# CarCharger.net
KiCad netlist of a schematic drawn in Altium Designer
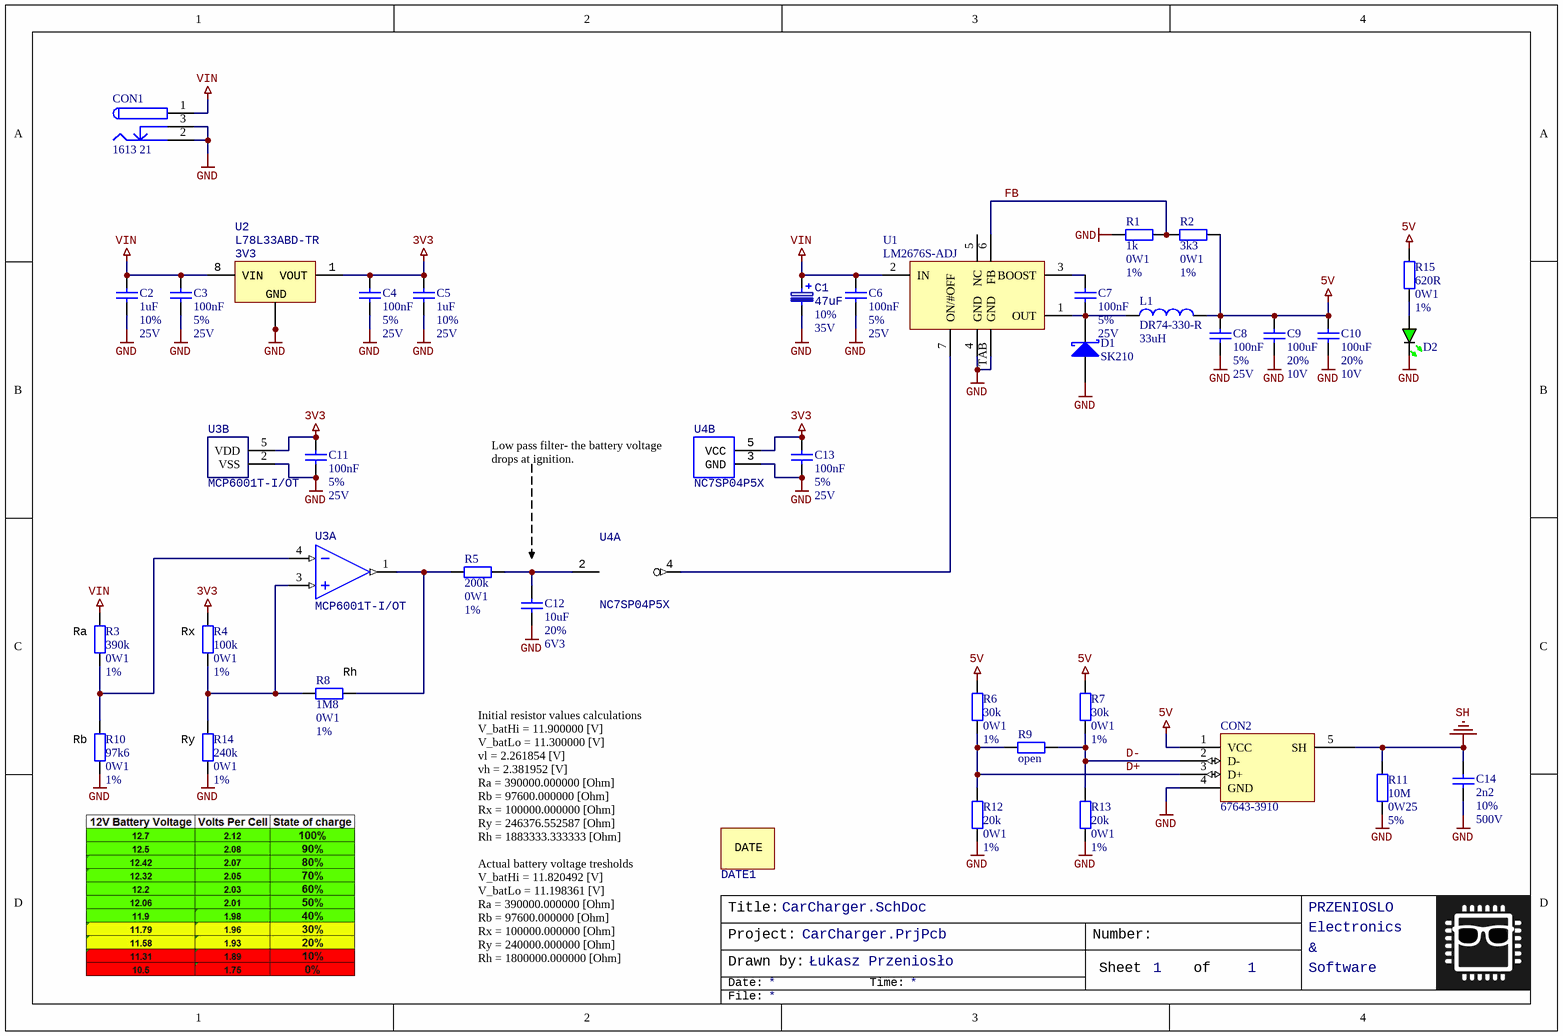
[diagram p0: CarCharger.SchDoc]

(export (version "E")
  (design (tool "Eeschema 10.0.6"))
  (components
    (comp (ref "C1")
      (value "47uF")
      (footprint "SMDD")
      (fields (field (name "TOLERANCE") "10%") (field (name "VOLTAGE") "35V"))
      (libsource (lib "passives") (part "cap_electro"))
    )
    (comp (ref "C2")
      (value "1uF")
      (footprint "CAPC1608N")
      (description "Capacitor")
      (fields (field (name "TOLERANCE") "10%") (field (name "VOLTAGE") "25V"))
      (libsource (lib "passives") (part "Capacitor"))
    )
    (comp (ref "C3")
      (value "100nF")
      (footprint "CAPC1608N")
      (description "Capacitor")
      (fields (field (name "TOLERANCE") "5%") (field (name "VOLTAGE") "25V"))
      (libsource (lib "passives") (part "Capacitor"))
    )
    (comp (ref "C4")
      (value "100nF")
      (footprint "CAPC1608N")
      (description "Capacitor")
      (fields (field (name "TOLERANCE") "5%") (field (name "VOLTAGE") "25V"))
      (libsource (lib "passives") (part "Capacitor"))
    )
    (comp (ref "C5")
      (value "1uF")
      (footprint "CAPC1608N")
      (description "Capacitor")
      (fields (field (name "TOLERANCE") "10%") (field (name "VOLTAGE") "25V"))
      (libsource (lib "passives") (part "Capacitor"))
    )
    (comp (ref "C6")
      (value "100nF")
      (footprint "CAPC1608N")
      (description "Capacitor")
      (fields (field (name "TOLERANCE") "5%") (field (name "VOLTAGE") "25V"))
      (libsource (lib "passives") (part "Capacitor"))
    )
    (comp (ref "C7")
      (value "100nF")
      (footprint "CAPC1608N")
      (description "Capacitor")
      (fields (field (name "TOLERANCE") "5%") (field (name "VOLTAGE") "25V"))
      (libsource (lib "passives") (part "Capacitor"))
    )
    (comp (ref "C8")
      (value "100nF")
      (footprint "CAPC1608N")
      (description "Capacitor")
      (fields (field (name "TOLERANCE") "5%") (field (name "VOLTAGE") "25V"))
      (libsource (lib "passives") (part "Capacitor"))
    )
    (comp (ref "C9")
      (value "100uF")
      (footprint "CAPC3225N")
      (description "Capacitor")
      (fields (field (name "TOLERANCE") "20%") (field (name "VOLTAGE") "10V"))
      (libsource (lib "passives") (part "Capacitor"))
    )
    (comp (ref "C10")
      (value "100uF")
      (footprint "CAPC3225N")
      (description "Capacitor")
      (fields (field (name "TOLERANCE") "20%") (field (name "VOLTAGE") "10V"))
      (libsource (lib "passives") (part "Capacitor"))
    )
    (comp (ref "C11")
      (value "100nF")
      (footprint "CAPC1608N")
      (description "Capacitor")
      (fields (field (name "TOLERANCE") "5%") (field (name "VOLTAGE") "25V"))
      (libsource (lib "passives") (part "Capacitor"))
    )
    (comp (ref "C12")
      (value "10uF")
      (footprint "CAPC1608N")
      (description "Capacitor")
      (fields (field (name "TOLERANCE") "20%") (field (name "VOLTAGE") "6V3"))
      (libsource (lib "passives") (part "Capacitor"))
    )
    (comp (ref "C13")
      (value "100nF")
      (footprint "CAPC1608N")
      (description "Capacitor")
      (fields (field (name "TOLERANCE") "5%") (field (name "VOLTAGE") "25V"))
      (libsource (lib "passives") (part "Capacitor"))
    )
    (comp (ref "C14")
      (value "2n2")
      (footprint "CAPC3216N")
      (description "Capacitor")
      (fields (field (name "TOLERANCE") "10%") (field (name "VOLTAGE") "500V"))
      (libsource (lib "passives") (part "Capacitor"))
    )
    (comp (ref "CON1")
      (value "1613 21")
      (footprint "JACK-2.5")
      (description "Low Voltage Power Supply Connector")
      (libsource (lib "connectors") (part "JACK-2.5"))
    )
    (comp (ref "CON2")
      (value "67643-3910")
      (footprint "USB-A-socket")
      (description "USB-A-Sock")
      (libsource (lib "connectors") (part "USB-A-Sock"))
    )
    (comp (ref "D1")
      (value "SK210")
      (footprint "SMB")
      (description "Schottky Barrier Rectifier,  40V, 3A")
      (libsource (lib "Mechatronic") (part "MBRS340T3"))
    )
    (comp (ref "D2")
      (value "Led Green")
      (footprint "CD2012-0805-GRN")
      (description "Typical GRN LED")
      (libsource (lib "semicon") (part "Led Green"))
    )
    (comp (ref "DATE1") (value "DATE") (footprint "DATE") (libsource (lib "misc") (part "DATE")))
    (comp (ref "L1")
      (value "DR74-330-R")
      (footprint "DR74 Series")
      (fields (field (name "ALTIUM_VALUE") "33uH") (field (name "PUBLISHER") "Altium Limited"))
      (libsource (lib "Mechatronic") (part "DR74-330-R"))
    )
    (comp (ref "R1")
      (value "1k")
      (footprint "RESC1608N")
      (description "Resistor")
      (fields (field (name "POWER") "0W1") (field (name "TOLERANCE") "1%"))
      (libsource (lib "") (part "Resistor_1"))
    )
    (comp (ref "R2")
      (value "3k3")
      (footprint "RESC1608N")
      (description "Resistor")
      (fields (field (name "POWER") "0W1") (field (name "TOLERANCE") "1%"))
      (libsource (lib "") (part "Resistor_1"))
    )
    (comp (ref "R3")
      (value "390k")
      (footprint "RESC1608N")
      (description "Resistor")
      (fields (field (name "POWER") "0W1") (field (name "TOLERANCE") "1%"))
      (libsource (lib "passives") (part "Resistor"))
    )
    (comp (ref "R4")
      (value "100k")
      (footprint "RESC1608N")
      (description "Resistor")
      (fields (field (name "POWER") "0W1") (field (name "TOLERANCE") "1%"))
      (libsource (lib "passives") (part "Resistor"))
    )
    (comp (ref "R5")
      (value "200k")
      (footprint "RESC1608N")
      (description "Resistor")
      (fields (field (name "POWER") "0W1") (field (name "TOLERANCE") "1%"))
      (libsource (lib "") (part "Resistor_1"))
    )
    (comp (ref "R6")
      (value "30k")
      (footprint "RESC1608N")
      (description "Resistor")
      (fields (field (name "POWER") "0W1") (field (name "TOLERANCE") "1%"))
      (libsource (lib "passives") (part "Resistor"))
    )
    (comp (ref "R7")
      (value "30k")
      (footprint "RESC1608N")
      (description "Resistor")
      (fields (field (name "POWER") "0W1") (field (name "TOLERANCE") "1%"))
      (libsource (lib "passives") (part "Resistor"))
    )
    (comp (ref "R8")
      (value "1M8")
      (footprint "RESC1608N")
      (description "Resistor")
      (fields (field (name "POWER") "0W1") (field (name "TOLERANCE") "1%"))
      (libsource (lib "") (part "Resistor_1"))
    )
    (comp (ref "R9")
      (value "open")
      (footprint "RESC1608N")
      (description "Resistor")
      (fields (field (name "TOLERANCE") "5%") (field (name "POWER") "0W"))
      (libsource (lib "Discrete") (part "Resistor"))
    )
    (comp (ref "R10")
      (value "97k6")
      (footprint "RESC1608N")
      (description "Resistor")
      (fields (field (name "POWER") "0W1") (field (name "TOLERANCE") "1%"))
      (libsource (lib "passives") (part "Resistor"))
    )
    (comp (ref "R11")
      (value "10M")
      (footprint "RESC3216N")
      (description "Resistor")
      (fields (field (name "POWER") "0W25") (field (name "TOLERANCE") "5%"))
      (libsource (lib "") (part "Resistor_1"))
    )
    (comp (ref "R12")
      (value "20k")
      (footprint "RESC1608N")
      (description "Resistor")
      (fields (field (name "POWER") "0W1") (field (name "TOLERANCE") "1%"))
      (libsource (lib "passives") (part "Resistor"))
    )
    (comp (ref "R13")
      (value "20k")
      (footprint "RESC1608N")
      (description "Resistor")
      (fields (field (name "POWER") "0W1") (field (name "TOLERANCE") "1%"))
      (libsource (lib "passives") (part "Resistor"))
    )
    (comp (ref "R14")
      (value "240k")
      (footprint "RESC1608N")
      (description "Resistor")
      (fields (field (name "POWER") "0W1") (field (name "TOLERANCE") "1%"))
      (libsource (lib "passives") (part "Resistor"))
    )
    (comp (ref "R15")
      (value "620R")
      (footprint "RESC1608N")
      (description "Resistor")
      (fields (field (name "POWER") "0W1") (field (name "TOLERANCE") "1%"))
      (libsource (lib "passives") (part "Resistor"))
    )
    (comp (ref "U1")
      (value "LM2676S-ADJ")
      (footprint "TO-263-7")
      (description "SIMPLE SWITCHER High Efficiency 3A Step-Down Voltage Regulator")
      (libsource (lib "power") (part "LM2676S-ADJ"))
    )
    (comp (ref "U2")
      (value "L78L33ABD-TR")
      (footprint "SO-8_L")
      (description "Positive voltage regulators")
      (fields (field (name "VOUT") "3V3"))
      (libsource (lib "power") (part "L78LXXAXD"))
    )
    (comp (ref "U3")
      (value "MCP6001T-I/OT")
      (footprint "SOT23-5_N")
      (description "1 MHz, Low-Power Op Amp")
      (libsource (lib "") (part "MCP6001_1"))
    )
    (comp (ref "U4")
      (value "NC7SP04P5X")
      (footprint "sc70")
      (description "tiny logic inverter")
      (libsource (lib "") (part "NC7SP04_1"))
    )
  )
  (nets
    (net (code "1") (name "/D+") (class "Default")
      (node (ref "CON2") (pin "3") (pinfunction "D+_3") (pintype "bidirectional"))
      (node (ref "R12") (pin "2") (pinfunction "2_2") (pintype "passive"))
      (node (ref "R6") (pin "1") (pinfunction "1_1") (pintype "passive"))
      (node (ref "R9") (pin "1") (pinfunction "1_1") (pintype "passive"))
    )
    (net (code "2") (name "/D-") (class "Default")
      (node (ref "CON2") (pin "2") (pinfunction "D-_2") (pintype "bidirectional"))
      (node (ref "R13") (pin "2") (pinfunction "2_2") (pintype "passive"))
      (node (ref "R7") (pin "1") (pinfunction "1_1") (pintype "passive"))
      (node (ref "R9") (pin "2") (pinfunction "2_2") (pintype "passive"))
    )
    (net (code "3") (name "/FB") (class "Default")
      (node (ref "R1") (pin "2") (pinfunction "2_2") (pintype "passive"))
      (node (ref "R2") (pin "1") (pinfunction "1_1") (pintype "passive"))
      (node (ref "U1") (pin "6") (pinfunction "FB_6") (pintype "passive"))
    )
    (net (code "4") (name "3V3") (class "Default")
      (node (ref "C11") (pin "2") (pinfunction "2_2") (pintype "passive"))
      (node (ref "C13") (pin "2") (pinfunction "2_2") (pintype "passive"))
      (node (ref "C4") (pin "2") (pinfunction "2_2") (pintype "passive"))
      (node (ref "C5") (pin "2") (pinfunction "2_2") (pintype "passive"))
      (node (ref "R4") (pin "2") (pinfunction "2_2") (pintype "passive"))
      (node (ref "U2") (pin "1") (pinfunction "VOUT_1") (pintype "power_in"))
      (node (ref "U3") (pin "5") (pinfunction "VDD_5") (pintype "power_in"))
      (node (ref "U4") (pin "5") (pinfunction "VCC_5") (pintype "power_in"))
    )
    (net (code "5") (name "5V") (class "Default")
      (node (ref "C10") (pin "1") (pinfunction "1_1") (pintype "passive"))
      (node (ref "C8") (pin "2") (pinfunction "2_2") (pintype "passive"))
      (node (ref "C9") (pin "1") (pinfunction "1_1") (pintype "passive"))
      (node (ref "CON2") (pin "1") (pinfunction "VCC_1") (pintype "power_in"))
      (node (ref "L1") (pin "2") (pinfunction "2_2") (pintype "passive"))
      (node (ref "R15") (pin "2") (pinfunction "2_2") (pintype "passive"))
      (node (ref "R2") (pin "2") (pinfunction "2_2") (pintype "passive"))
      (node (ref "R6") (pin "2") (pinfunction "2_2") (pintype "passive"))
      (node (ref "R7") (pin "2") (pinfunction "2_2") (pintype "passive"))
    )
    (net (code "6") (name "GND") (class "Default")
      (node (ref "C1") (pin "2") (pinfunction "2_2") (pintype "passive"))
      (node (ref "C10") (pin "2") (pinfunction "2_2") (pintype "passive"))
      (node (ref "C11") (pin "1") (pinfunction "1_1") (pintype "passive"))
      (node (ref "C12") (pin "1") (pinfunction "1_1") (pintype "passive"))
      (node (ref "C13") (pin "1") (pinfunction "1_1") (pintype "passive"))
      (node (ref "C14") (pin "1") (pinfunction "1_1") (pintype "passive"))
      (node (ref "C2") (pin "1") (pinfunction "1_1") (pintype "passive"))
      (node (ref "C3") (pin "1") (pinfunction "1_1") (pintype "passive"))
      (node (ref "C4") (pin "1") (pinfunction "1_1") (pintype "passive"))
      (node (ref "C5") (pin "1") (pinfunction "1_1") (pintype "passive"))
      (node (ref "C6") (pin "1") (pinfunction "1_1") (pintype "passive"))
      (node (ref "C8") (pin "1") (pinfunction "1_1") (pintype "passive"))
      (node (ref "C9") (pin "2") (pinfunction "2_2") (pintype "passive"))
      (node (ref "CON1") (pin "2") (pinfunction "2_2") (pintype "power_in"))
      (node (ref "CON1") (pin "3") (pinfunction "3_3") (pintype "passive"))
      (node (ref "CON2") (pin "4") (pinfunction "GND_4") (pintype "power_in"))
      (node (ref "D1") (pin "1") (pinfunction "A_1") (pintype "passive"))
      (node (ref "D2") (pin "2") (pinfunction "K_2") (pintype "passive"))
      (node (ref "R1") (pin "1") (pinfunction "1_1") (pintype "passive"))
      (node (ref "R10") (pin "1") (pinfunction "1_1") (pintype "passive"))
      (node (ref "R11") (pin "1") (pinfunction "1_1") (pintype "passive"))
      (node (ref "R12") (pin "1") (pinfunction "1_1") (pintype "passive"))
      (node (ref "R13") (pin "1") (pinfunction "1_1") (pintype "passive"))
      (node (ref "R14") (pin "1") (pinfunction "1_1") (pintype "passive"))
      (node (ref "U1") (pin "4") (pinfunction "GND_4") (pintype "passive"))
      (node (ref "U1") (pin "TAB") (pinfunction "GND_TAB") (pintype "passive"))
      (node (ref "U2") (pin "2") (pinfunction "GND_2") (pintype "power_in"))
      (node (ref "U2") (pin "3") (pinfunction "GND_3") (pintype "power_in"))
      (node (ref "U2") (pin "6") (pinfunction "GND_6") (pintype "power_in"))
      (node (ref "U2") (pin "7") (pinfunction "GND_7") (pintype "power_in"))
      (node (ref "U3") (pin "2") (pinfunction "VSS_2") (pintype "power_in"))
      (node (ref "U4") (pin "3") (pinfunction "GND_3") (pintype "power_in"))
    )
    (net (code "7") (name "Net-(D1-K)") (class "Default")
      (node (ref "C7") (pin "1") (pinfunction "1_1") (pintype "passive"))
      (node (ref "D1") (pin "2") (pinfunction "K_2") (pintype "passive"))
      (node (ref "L1") (pin "1") (pinfunction "1_1") (pintype "passive"))
      (node (ref "U1") (pin "1") (pinfunction "OUT_1") (pintype "passive"))
    )
    (net (code "8") (name "Net-(D2-A)") (class "Default")
      (node (ref "D2") (pin "1") (pinfunction "A_1") (pintype "passive"))
      (node (ref "R15") (pin "1") (pinfunction "1_1") (pintype "passive"))
    )
    (net (code "9") (name "Net-(U1-BOOST)") (class "Default")
      (node (ref "C7") (pin "2") (pinfunction "2_2") (pintype "passive"))
      (node (ref "U1") (pin "3") (pinfunction "BOOST_3") (pintype "passive"))
    )
    (net (code "10") (name "Net-(U1-ON{slash}#OFF)") (class "Default")
      (node (ref "U1") (pin "7") (pinfunction "ON/#OFF_7") (pintype "passive"))
      (node (ref "U4") (pin "4") (pinfunction "Y_4") (pintype "output"))
    )
    (net (code "11") (name "Net-(U3A-+IN)") (class "Default")
      (node (ref "R14") (pin "2") (pinfunction "2_2") (pintype "passive"))
      (node (ref "R4") (pin "1") (pinfunction "1_1") (pintype "passive"))
      (node (ref "R8") (pin "1") (pinfunction "1_1") (pintype "passive"))
      (node (ref "U3") (pin "3") (pinfunction "+IN_3") (pintype "input"))
    )
    (net (code "12") (name "Net-(U3A--IN)") (class "Default")
      (node (ref "R10") (pin "2") (pinfunction "2_2") (pintype "passive"))
      (node (ref "R3") (pin "1") (pinfunction "1_1") (pintype "passive"))
      (node (ref "U3") (pin "4") (pinfunction "-IN_4") (pintype "input"))
    )
    (net (code "13") (name "Net-(U3A-OUT)") (class "Default")
      (node (ref "R5") (pin "1") (pinfunction "1_1") (pintype "passive"))
      (node (ref "R8") (pin "2") (pinfunction "2_2") (pintype "passive"))
      (node (ref "U3") (pin "1") (pinfunction "OUT_1") (pintype "output"))
    )
    (net (code "14") (name "Net-(U4A-A)") (class "Default")
      (node (ref "C12") (pin "2") (pinfunction "2_2") (pintype "passive"))
      (node (ref "R5") (pin "2") (pinfunction "2_2") (pintype "passive"))
      (node (ref "U4") (pin "2") (pinfunction "A_2") (pintype "power_in"))
    )
    (net (code "15") (name "SH") (class "Default")
      (node (ref "C14") (pin "2") (pinfunction "2_2") (pintype "passive"))
      (node (ref "CON2") (pin "5") (pinfunction "SH_5") (pintype "passive"))
      (node (ref "R11") (pin "2") (pinfunction "2_2") (pintype "passive"))
    )
    (net (code "16") (name "VIN") (class "Default")
      (node (ref "C1") (pin "1") (pinfunction "1_1") (pintype "passive"))
      (node (ref "C2") (pin "2") (pinfunction "2_2") (pintype "passive"))
      (node (ref "C3") (pin "2") (pinfunction "2_2") (pintype "passive"))
      (node (ref "C6") (pin "2") (pinfunction "2_2") (pintype "passive"))
      (node (ref "CON1") (pin "1") (pinfunction "1_1") (pintype "power_in"))
      (node (ref "R3") (pin "2") (pinfunction "2_2") (pintype "passive"))
      (node (ref "U1") (pin "2") (pinfunction "IN_2") (pintype "passive"))
      (node (ref "U2") (pin "8") (pinfunction "VIN_8") (pintype "power_in"))
    )
    (net (code "17") (name "unconnected-(U1-NC-Pad5)") (class "Default")
      (node (ref "U1") (pin "5") (pinfunction "NC_5") (pintype "passive"))
    )
    (net (code "18") (name "unconnected-(U4A-NC-Pad1)") (class "Default")
      (node (ref "U4") (pin "1") (pinfunction "NC_1") (pintype "passive"))
    )
  )
)
